# NTC_Sense_V0_1.net
KiCad netlist of a schematic drawn in Altium Designer
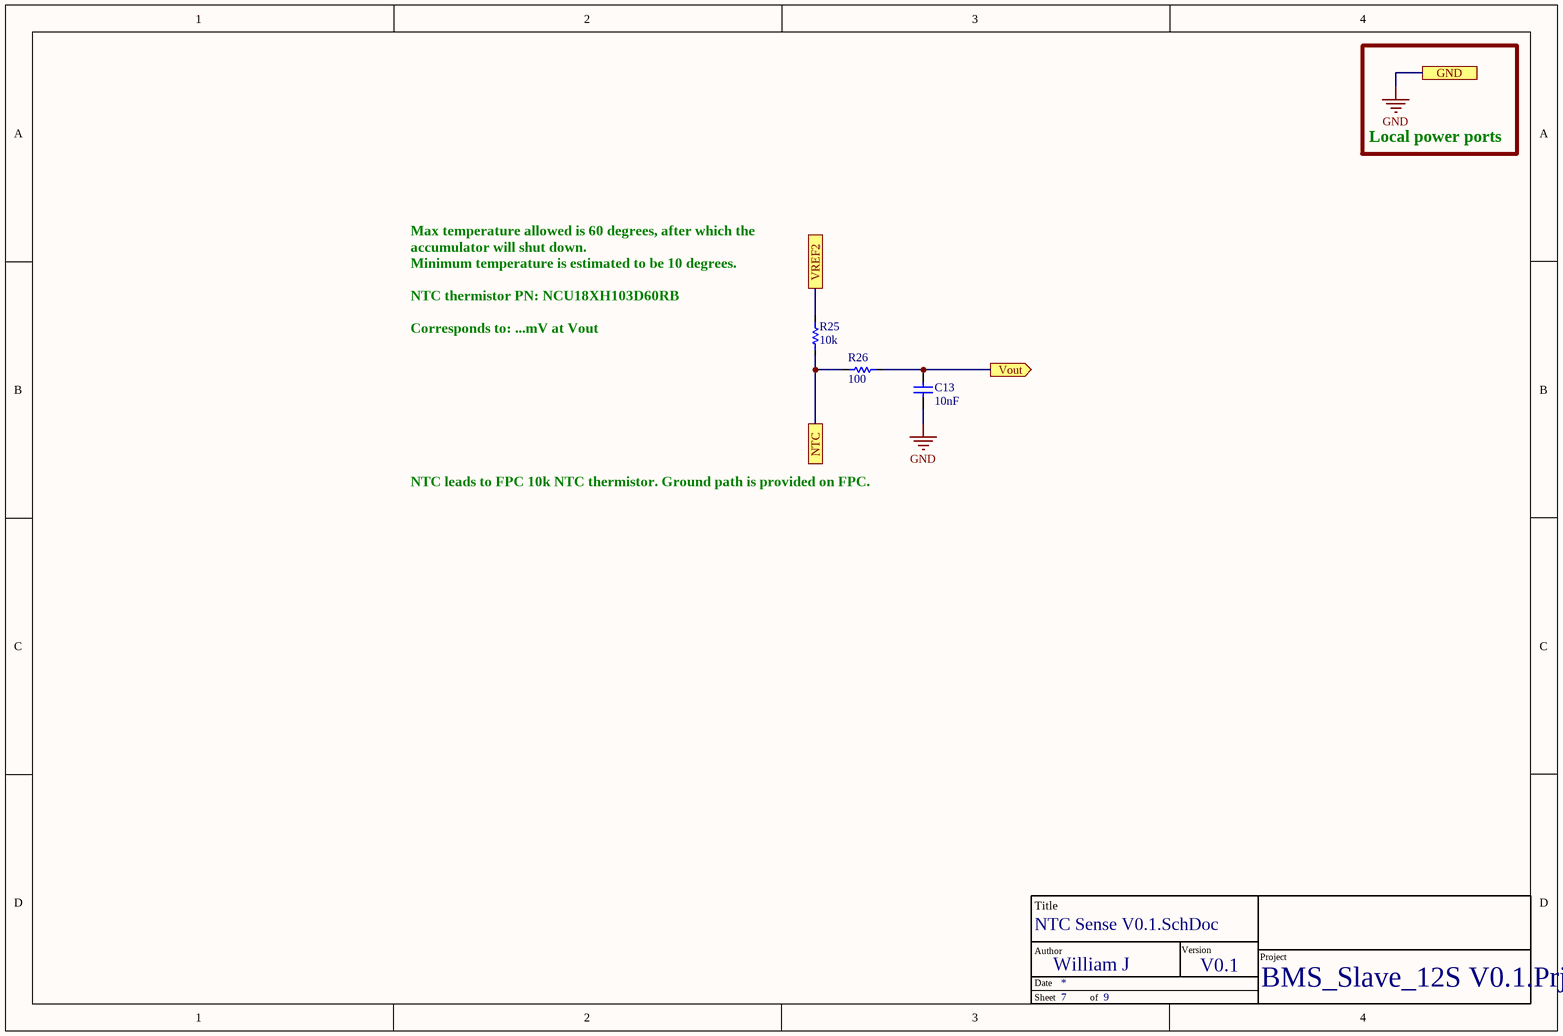
[diagram p0: NTC Sense V0.1.SchDoc]

(export (version "E")
  (design (tool "Eeschema 10.0.6"))
  (components
    (comp (ref "*") (value "TitleBlock") (libsource (lib "SchematicLib") (part "TitleBlock")))
    (comp (ref "C13")
      (value "10nF")
      (footprint "C_0402")
      (description "Capacitor")
      (fields (field (name "Comment") "C1005X7S2A103K050BB"))
      (libsource (lib "Passives") (part "Capacitor"))
    )
    (comp (ref "R25")
      (value "10k")
      (footprint "R_0402")
      (description "Resistor")
      (fields (field (name "Comment") "RC0402FR-1310KL"))
      (libsource (lib "Passives") (part "Resistor"))
    )
    (comp (ref "R26")
      (value "100")
      (footprint "R_0402")
      (description "Resistor")
      (fields (field (name "Comment") "RC0402FR-07100RL"))
      (libsource (lib "Passives") (part "Resistor"))
    )
  )
  (nets
    (net (code "1") (name "/NTC") (class "Default")
      (node (ref "R25") (pin "1") (pinfunction "1_1") (pintype "passive"))
      (node (ref "R26") (pin "2") (pinfunction "2_2") (pintype "passive"))
    )
    (net (code "2") (name "/VREF2") (class "Default")
      (node (ref "R25") (pin "2") (pinfunction "2_2") (pintype "passive"))
    )
    (net (code "3") (name "/Vout") (class "Default")
      (node (ref "C13") (pin "2") (pinfunction "2_2") (pintype "passive"))
      (node (ref "R26") (pin "1") (pinfunction "1_1") (pintype "passive"))
    )
    (net (code "4") (name "GND") (class "Default")
      (node (ref "C13") (pin "1") (pinfunction "1_1") (pintype "passive"))
    )
  )
)
